# OBD_Reader.net
KiCad netlist of a schematic drawn in EAGLE
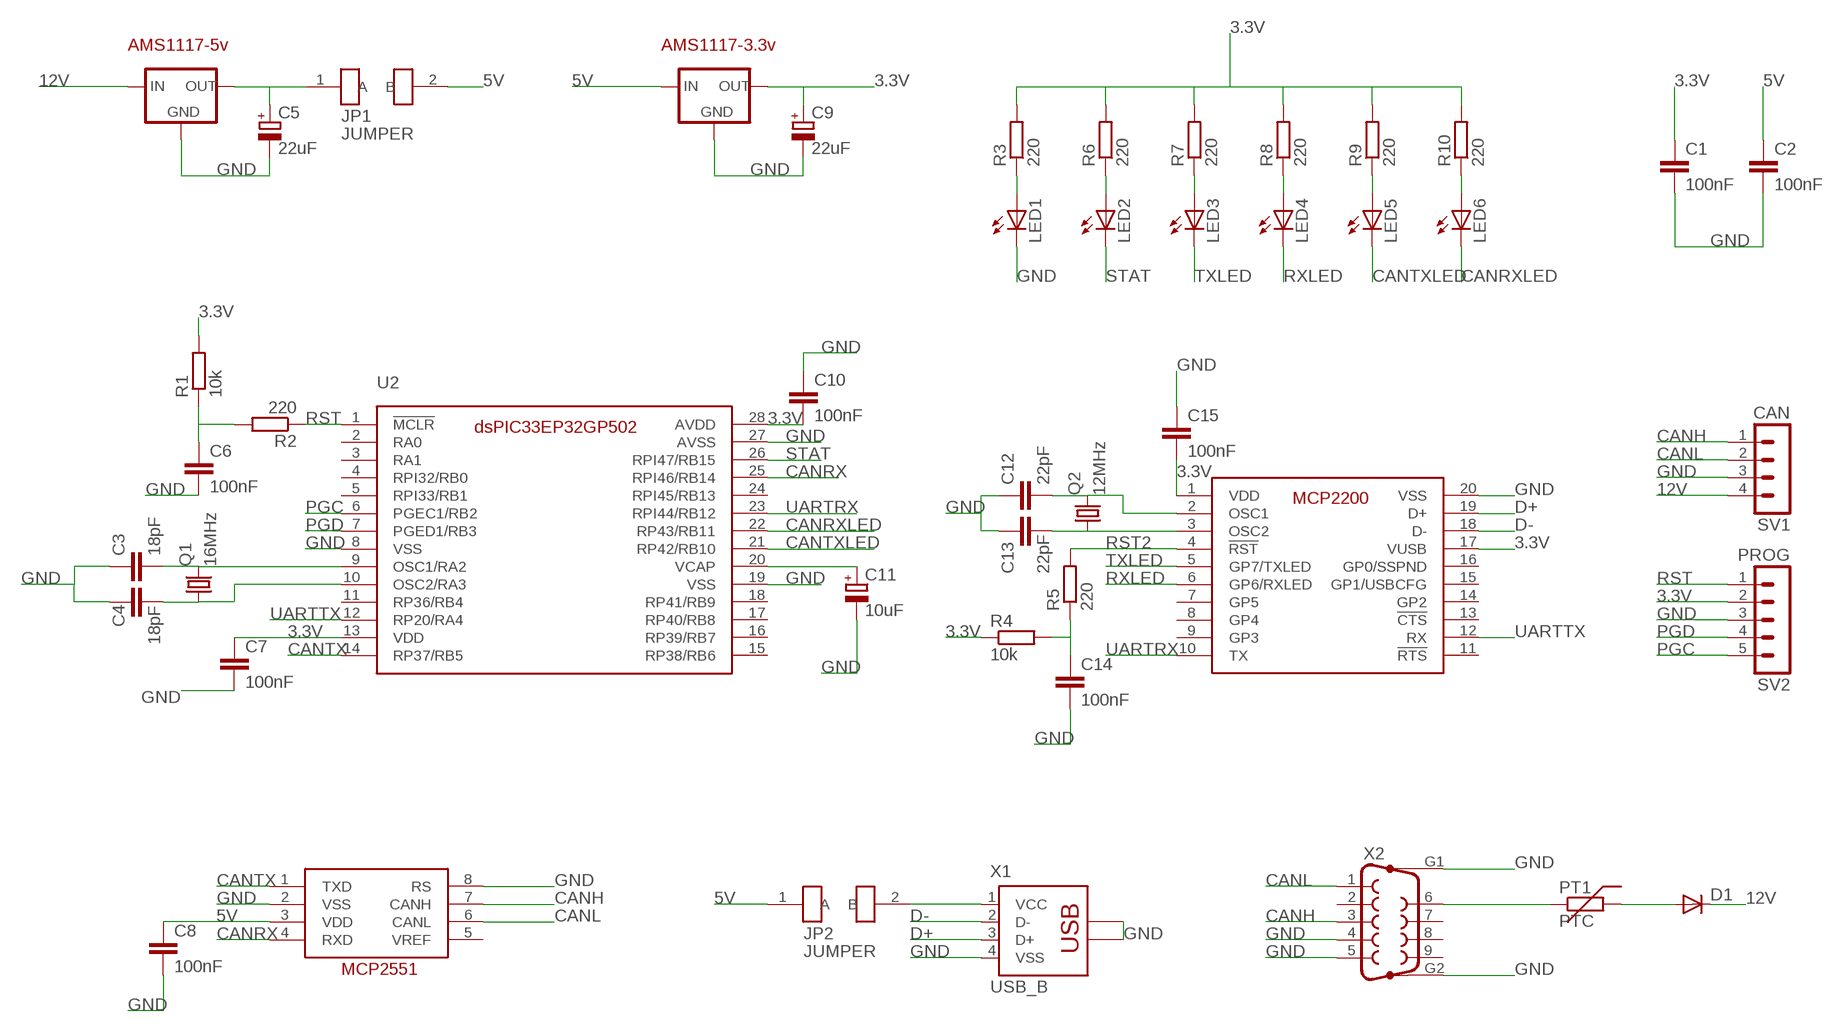
[diagram p0: schematic, sheet 1]

(export (version "E")
  (design (tool "Eeschema 10.0.6"))
  (components
    (comp (ref "C1")
      (value "100nF")
      (footprint "eagle-import:C0603")
      (libsource (lib "eagle-import") (part "C-EUC0603"))
    )
    (comp (ref "C2")
      (value "100nF")
      (footprint "eagle-import:C0603")
      (libsource (lib "eagle-import") (part "C-EUC0603"))
    )
    (comp (ref "C3")
      (value "18pF")
      (footprint "eagle-import:C0603")
      (libsource (lib "eagle-import") (part "C-EUC0603"))
    )
    (comp (ref "C4")
      (value "18pF")
      (footprint "eagle-import:C0603")
      (libsource (lib "eagle-import") (part "C-EUC0603"))
    )
    (comp (ref "C5")
      (value "22uF")
      (footprint "eagle-import:CT3216")
      (libsource (lib "eagle-import") (part "CPOL-EUCT3216"))
    )
    (comp (ref "C6")
      (value "100nF")
      (footprint "eagle-import:C0603")
      (libsource (lib "eagle-import") (part "C-EUC0603"))
    )
    (comp (ref "C7")
      (value "100nF")
      (footprint "eagle-import:C0603")
      (libsource (lib "eagle-import") (part "C-EUC0603"))
    )
    (comp (ref "C8")
      (value "100nF")
      (footprint "eagle-import:C0603")
      (libsource (lib "eagle-import") (part "C-EUC0603"))
    )
    (comp (ref "C9")
      (value "22uF")
      (footprint "eagle-import:CT3216")
      (libsource (lib "eagle-import") (part "CPOL-EUCT3216"))
    )
    (comp (ref "C10")
      (value "100nF")
      (footprint "eagle-import:C0603")
      (libsource (lib "eagle-import") (part "C-EUC0603"))
    )
    (comp (ref "C11")
      (value "10uF")
      (footprint "eagle-import:CT3216")
      (libsource (lib "eagle-import") (part "CPOL-EUCT3216"))
    )
    (comp (ref "C12")
      (value "22pF")
      (footprint "eagle-import:C0603")
      (libsource (lib "eagle-import") (part "C-EUC0603"))
    )
    (comp (ref "C13")
      (value "22pF")
      (footprint "eagle-import:C0603")
      (libsource (lib "eagle-import") (part "C-EUC0603"))
    )
    (comp (ref "C14")
      (value "100nF")
      (footprint "eagle-import:C0603")
      (libsource (lib "eagle-import") (part "C-EUC0603"))
    )
    (comp (ref "C15")
      (value "100nF")
      (footprint "eagle-import:C0603")
      (libsource (lib "eagle-import") (part "C-EUC0603"))
    )
    (comp (ref "D1")
      (value "DIODE-SMB")
      (footprint "eagle-import:SMB")
      (libsource (lib "eagle-import") (part "DIODE-SMB"))
    )
    (comp (ref "JP1")
      (value "JUMPER")
      (footprint "eagle-import:1206")
      (libsource (lib "eagle-import") (part "JUMPER"))
    )
    (comp (ref "JP2")
      (value "JUMPER")
      (footprint "eagle-import:1206")
      (libsource (lib "eagle-import") (part "JUMPER"))
    )
    (comp (ref "LED1")
      (value "LEDCHIPLED_0603")
      (footprint "eagle-import:CHIPLED_0603")
      (libsource (lib "eagle-import") (part "LEDCHIPLED_0603"))
    )
    (comp (ref "LED2")
      (value "LEDCHIPLED_0603")
      (footprint "eagle-import:CHIPLED_0603")
      (libsource (lib "eagle-import") (part "LEDCHIPLED_0603"))
    )
    (comp (ref "LED3")
      (value "LEDCHIPLED_0603")
      (footprint "eagle-import:CHIPLED_0603")
      (libsource (lib "eagle-import") (part "LEDCHIPLED_0603"))
    )
    (comp (ref "LED4")
      (value "LEDCHIPLED_0603")
      (footprint "eagle-import:CHIPLED_0603")
      (libsource (lib "eagle-import") (part "LEDCHIPLED_0603"))
    )
    (comp (ref "LED5")
      (value "LEDCHIPLED_0603")
      (footprint "eagle-import:CHIPLED_0603")
      (libsource (lib "eagle-import") (part "LEDCHIPLED_0603"))
    )
    (comp (ref "LED6")
      (value "LEDCHIPLED_0603")
      (footprint "eagle-import:CHIPLED_0603")
      (libsource (lib "eagle-import") (part "LEDCHIPLED_0603"))
    )
    (comp (ref "PT1")
      (value "PTC")
      (footprint "eagle-import:PTC_1206")
      (libsource (lib "eagle-import") (part "PTC"))
    )
    (comp (ref "Q1")
      (value "16MHz")
      (footprint "eagle-import:HC49_S")
      (libsource (lib "eagle-import") (part "CRYSTALHC49S"))
    )
    (comp (ref "Q2")
      (value "12MHz")
      (footprint "eagle-import:HC49_S")
      (libsource (lib "eagle-import") (part "CRYSTALHC49S"))
    )
    (comp (ref "R1")
      (value "10k")
      (footprint "eagle-import:R0603")
      (libsource (lib "eagle-import") (part "R-EU_R0603"))
    )
    (comp (ref "R2")
      (value "220")
      (footprint "eagle-import:R0603")
      (libsource (lib "eagle-import") (part "R-EU_R0603"))
    )
    (comp (ref "R3")
      (value "220")
      (footprint "eagle-import:R0603")
      (libsource (lib "eagle-import") (part "R-EU_R0603"))
    )
    (comp (ref "R4")
      (value "10k")
      (footprint "eagle-import:R0603")
      (libsource (lib "eagle-import") (part "R-EU_R0603"))
    )
    (comp (ref "R5")
      (value "220")
      (footprint "eagle-import:R0603")
      (libsource (lib "eagle-import") (part "R-EU_R0603"))
    )
    (comp (ref "R6")
      (value "220")
      (footprint "eagle-import:R0603")
      (libsource (lib "eagle-import") (part "R-EU_R0603"))
    )
    (comp (ref "R7")
      (value "220")
      (footprint "eagle-import:R0603")
      (libsource (lib "eagle-import") (part "R-EU_R0603"))
    )
    (comp (ref "R8")
      (value "220")
      (footprint "eagle-import:R0603")
      (libsource (lib "eagle-import") (part "R-EU_R0603"))
    )
    (comp (ref "R9")
      (value "220")
      (footprint "eagle-import:R0603")
      (libsource (lib "eagle-import") (part "R-EU_R0603"))
    )
    (comp (ref "R10")
      (value "220")
      (footprint "eagle-import:R0603")
      (libsource (lib "eagle-import") (part "R-EU_R0603"))
    )
    (comp (ref "SV1")
      (value "CAN")
      (footprint "eagle-import:MA04-1")
      (libsource (lib "eagle-import") (part "MA04-1"))
    )
    (comp (ref "SV2")
      (value "PROG")
      (footprint "eagle-import:MA05-1")
      (libsource (lib "eagle-import") (part "MA05-1"))
    )
    (comp (ref "U1")
      (value "AMS1117_5V")
      (footprint "eagle-import:SOT-223")
      (libsource (lib "eagle-import") (part "AMS1117_5V"))
    )
    (comp (ref "U2")
      (value "DSPIC33EP32GP502")
      (footprint "eagle-import:SSOP28")
      (libsource (lib "eagle-import") (part "DSPIC33EP32GP502"))
    )
    (comp (ref "U3")
      (value "MCP2551")
      (footprint "eagle-import:SOIC20")
      (libsource (lib "eagle-import") (part "MCP2551"))
    )
    (comp (ref "U4")
      (value "AMS1117_3.3V")
      (footprint "eagle-import:SOT-223")
      (libsource (lib "eagle-import") (part "AMS1117_3.3V"))
    )
    (comp (ref "U5")
      (value "MCP2200")
      (footprint "eagle-import:SSOP20")
      (libsource (lib "eagle-import") (part "MCP2200"))
    )
    (comp (ref "X1")
      (value "USB_B")
      (footprint "eagle-import:85-32004-00X")
      (libsource (lib "eagle-import") (part "USB_B"))
    )
    (comp (ref "X2")
      (value "F09HP")
      (footprint "eagle-import:F09HP")
      (libsource (lib "eagle-import") (part "F09HP"))
    )
  )
  (nets
    (net (code "1") (name "/3.3V") (class "Default")
      (node (ref "C1") (pin "1") (pinfunction "1_1") (pintype "passive"))
      (node (ref "C10") (pin "2") (pinfunction "2_2") (pintype "passive"))
      (node (ref "C15") (pin "2") (pinfunction "2_2") (pintype "passive"))
      (node (ref "C7") (pin "1") (pinfunction "1_1") (pintype "passive"))
      (node (ref "C9") (pin "+") (pinfunction "+_+") (pintype "passive"))
      (node (ref "R1") (pin "2") (pinfunction "2_2") (pintype "passive"))
      (node (ref "R10") (pin "2") (pinfunction "2_2") (pintype "passive"))
      (node (ref "R3") (pin "2") (pinfunction "2_2") (pintype "passive"))
      (node (ref "R4") (pin "1") (pinfunction "1_1") (pintype "passive"))
      (node (ref "R6") (pin "2") (pinfunction "2_2") (pintype "passive"))
      (node (ref "R7") (pin "2") (pinfunction "2_2") (pintype "passive"))
      (node (ref "R8") (pin "2") (pinfunction "2_2") (pintype "passive"))
      (node (ref "R9") (pin "2") (pinfunction "2_2") (pintype "passive"))
      (node (ref "SV2") (pin "2") (pinfunction "2_2") (pintype "passive"))
      (node (ref "U2") (pin "13") (pinfunction "VDD_13") (pintype "power_in"))
      (node (ref "U2") (pin "28") (pinfunction "AVDD_28") (pintype "power_in"))
      (node (ref "U4") (pin "2") (pinfunction "OUT_2") (pintype "passive"))
      (node (ref "U5") (pin "1") (pinfunction "VDD_1") (pintype "power_in"))
      (node (ref "U5") (pin "17") (pinfunction "VUSB_17") (pintype "power_in"))
    )
    (net (code "2") (name "/5V") (class "Default")
      (node (ref "C2") (pin "1") (pinfunction "1_1") (pintype "passive"))
      (node (ref "C8") (pin "1") (pinfunction "1_1") (pintype "passive"))
      (node (ref "JP1") (pin "2") (pinfunction "B_2") (pintype "power_in"))
      (node (ref "JP2") (pin "1") (pinfunction "A_1") (pintype "power_in"))
      (node (ref "U3") (pin "3") (pinfunction "VDD_3") (pintype "power_in"))
      (node (ref "U4") (pin "3") (pinfunction "IN_3") (pintype "input"))
    )
    (net (code "3") (name "/12V") (class "Default")
      (node (ref "D1") (pin "C") (pinfunction "C_C") (pintype "passive"))
      (node (ref "SV1") (pin "4") (pinfunction "4_4") (pintype "passive"))
      (node (ref "U1") (pin "3") (pinfunction "IN_3") (pintype "input"))
    )
    (net (code "4") (name "/CANH") (class "Default")
      (node (ref "SV1") (pin "1") (pinfunction "1_1") (pintype "passive"))
      (node (ref "U3") (pin "7") (pinfunction "CANH_7") (pintype "bidirectional"))
      (node (ref "X2") (pin "3") (pinfunction "3_3") (pintype "passive"))
    )
    (net (code "5") (name "/CANL") (class "Default")
      (node (ref "SV1") (pin "2") (pinfunction "2_2") (pintype "passive"))
      (node (ref "U3") (pin "6") (pinfunction "CANL_6") (pintype "bidirectional"))
      (node (ref "X2") (pin "1") (pinfunction "1_1") (pintype "passive"))
    )
    (net (code "6") (name "/CANRX") (class "Default")
      (node (ref "U2") (pin "25") (pinfunction "RPI46/RB14_25") (pintype "bidirectional"))
      (node (ref "U3") (pin "4") (pinfunction "RXD_4") (pintype "bidirectional"))
    )
    (net (code "7") (name "/CANRXLED") (class "Default")
      (node (ref "LED6") (pin "C") (pinfunction "C_C") (pintype "passive"))
      (node (ref "U2") (pin "22") (pinfunction "RP43/RB11_22") (pintype "bidirectional"))
    )
    (net (code "8") (name "/CANTX") (class "Default")
      (node (ref "U2") (pin "14") (pinfunction "RP37/RB5_14") (pintype "bidirectional"))
      (node (ref "U3") (pin "1") (pinfunction "TXD_1") (pintype "bidirectional"))
    )
    (net (code "9") (name "/CANTXLED") (class "Default")
      (node (ref "LED5") (pin "C") (pinfunction "C_C") (pintype "passive"))
      (node (ref "U2") (pin "21") (pinfunction "RP42/RB10_21") (pintype "bidirectional"))
    )
    (net (code "10") (name "/D+") (class "Default")
      (node (ref "U5") (pin "19") (pinfunction "D+_19") (pintype "bidirectional"))
      (node (ref "X1") (pin "3") (pinfunction "D+_3") (pintype "passive"))
    )
    (net (code "11") (name "/D-") (class "Default")
      (node (ref "U5") (pin "18") (pinfunction "D-_18") (pintype "bidirectional"))
      (node (ref "X1") (pin "2") (pinfunction "D-_2") (pintype "passive"))
    )
    (net (code "12") (name "/GND") (class "Default")
      (node (ref "C1") (pin "2") (pinfunction "2_2") (pintype "passive"))
      (node (ref "C10") (pin "1") (pinfunction "1_1") (pintype "passive"))
      (node (ref "C11") (pin "-") (pinfunction "-_-") (pintype "passive"))
      (node (ref "C12") (pin "1") (pinfunction "1_1") (pintype "passive"))
      (node (ref "C13") (pin "1") (pinfunction "1_1") (pintype "passive"))
      (node (ref "C14") (pin "2") (pinfunction "2_2") (pintype "passive"))
      (node (ref "C15") (pin "1") (pinfunction "1_1") (pintype "passive"))
      (node (ref "C2") (pin "2") (pinfunction "2_2") (pintype "passive"))
      (node (ref "C3") (pin "1") (pinfunction "1_1") (pintype "passive"))
      (node (ref "C4") (pin "1") (pinfunction "1_1") (pintype "passive"))
      (node (ref "C5") (pin "-") (pinfunction "-_-") (pintype "passive"))
      (node (ref "C6") (pin "2") (pinfunction "2_2") (pintype "passive"))
      (node (ref "C7") (pin "2") (pinfunction "2_2") (pintype "passive"))
      (node (ref "C8") (pin "2") (pinfunction "2_2") (pintype "passive"))
      (node (ref "C9") (pin "-") (pinfunction "-_-") (pintype "passive"))
      (node (ref "LED1") (pin "C") (pinfunction "C_C") (pintype "passive"))
      (node (ref "SV1") (pin "3") (pinfunction "3_3") (pintype "passive"))
      (node (ref "SV2") (pin "3") (pinfunction "3_3") (pintype "passive"))
      (node (ref "U1") (pin "1") (pinfunction "GND_1") (pintype "input"))
      (node (ref "U2") (pin "19") (pinfunction "VSS_19") (pintype "power_in"))
      (node (ref "U2") (pin "27") (pinfunction "AVSS_27") (pintype "power_in"))
      (node (ref "U2") (pin "8") (pinfunction "VSS_8") (pintype "power_in"))
      (node (ref "U3") (pin "2") (pinfunction "VSS_2") (pintype "power_in"))
      (node (ref "U3") (pin "8") (pinfunction "RS_8") (pintype "bidirectional"))
      (node (ref "U4") (pin "1") (pinfunction "GND_1") (pintype "input"))
      (node (ref "U5") (pin "20") (pinfunction "VSS_20") (pintype "power_in"))
      (node (ref "X1") (pin "4") (pinfunction "VSS_4") (pintype "passive"))
      (node (ref "X1") (pin "M1") (pinfunction "C1_M1") (pintype "bidirectional"))
      (node (ref "X1") (pin "M2") (pinfunction "C2_M2") (pintype "bidirectional"))
      (node (ref "X2") (pin "4") (pinfunction "4_4") (pintype "passive"))
      (node (ref "X2") (pin "5") (pinfunction "5_5") (pintype "passive"))
      (node (ref "X2") (pin "G1") (pinfunction "G1_G1") (pintype "passive"))
      (node (ref "X2") (pin "G2") (pinfunction "G2_G2") (pintype "passive"))
    )
    (net (code "13") (name "/PGC") (class "Default")
      (node (ref "SV2") (pin "5") (pinfunction "5_5") (pintype "passive"))
      (node (ref "U2") (pin "6") (pinfunction "PGEC1/RB2_6") (pintype "bidirectional"))
    )
    (net (code "14") (name "/PGD") (class "Default")
      (node (ref "SV2") (pin "4") (pinfunction "4_4") (pintype "passive"))
      (node (ref "U2") (pin "7") (pinfunction "PGED1/RB3_7") (pintype "bidirectional"))
    )
    (net (code "15") (name "/RST") (class "Default")
      (node (ref "R2") (pin "1") (pinfunction "1_1") (pintype "passive"))
      (node (ref "SV2") (pin "1") (pinfunction "1_1") (pintype "passive"))
      (node (ref "U2") (pin "1") (pinfunction "~{MCLR}_1") (pintype "input"))
    )
    (net (code "16") (name "/RST2") (class "Default")
      (node (ref "R5") (pin "2") (pinfunction "2_2") (pintype "passive"))
      (node (ref "U5") (pin "4") (pinfunction "~{RST}_4") (pintype "input"))
    )
    (net (code "17") (name "/RXLED") (class "Default")
      (node (ref "LED4") (pin "C") (pinfunction "C_C") (pintype "passive"))
      (node (ref "U5") (pin "6") (pinfunction "GP6/RXLED_6") (pintype "bidirectional"))
    )
    (net (code "18") (name "/STAT") (class "Default")
      (node (ref "LED2") (pin "C") (pinfunction "C_C") (pintype "passive"))
      (node (ref "U2") (pin "26") (pinfunction "RPI47/RB15_26") (pintype "bidirectional"))
    )
    (net (code "19") (name "/TXLED") (class "Default")
      (node (ref "LED3") (pin "C") (pinfunction "C_C") (pintype "passive"))
      (node (ref "U5") (pin "5") (pinfunction "GP7/TXLED_5") (pintype "bidirectional"))
    )
    (net (code "20") (name "/UARTRX") (class "Default")
      (node (ref "U2") (pin "23") (pinfunction "RPI44/RB12_23") (pintype "bidirectional"))
      (node (ref "U5") (pin "10") (pinfunction "TX_10") (pintype "bidirectional"))
    )
    (net (code "21") (name "/UARTTX") (class "Default")
      (node (ref "U2") (pin "12") (pinfunction "RP20/RA4_12") (pintype "bidirectional"))
      (node (ref "U5") (pin "12") (pinfunction "RX_12") (pintype "bidirectional"))
    )
    (net (code "22") (name "Net-(C6-Pad1)") (class "Default")
      (node (ref "C6") (pin "1") (pinfunction "1_1") (pintype "passive"))
      (node (ref "R1") (pin "1") (pinfunction "1_1") (pintype "passive"))
      (node (ref "R2") (pin "2") (pinfunction "2_2") (pintype "passive"))
    )
    (net (code "23") (name "Net-(C14-Pad1)") (class "Default")
      (node (ref "C14") (pin "1") (pinfunction "1_1") (pintype "passive"))
      (node (ref "R4") (pin "2") (pinfunction "2_2") (pintype "passive"))
      (node (ref "R5") (pin "1") (pinfunction "1_1") (pintype "passive"))
    )
    (net (code "24") (name "Net-(D1-PadA)") (class "Default")
      (node (ref "D1") (pin "A") (pinfunction "A_A") (pintype "passive"))
      (node (ref "PT1") (pin "2") (pinfunction "2_2") (pintype "passive"))
    )
    (net (code "25") (name "Net-(JP1-A)") (class "Default")
      (node (ref "C5") (pin "+") (pinfunction "+_+") (pintype "passive"))
      (node (ref "JP1") (pin "1") (pinfunction "A_1") (pintype "power_in"))
      (node (ref "U1") (pin "2") (pinfunction "OUT_2") (pintype "passive"))
    )
    (net (code "26") (name "Net-(JP2-B)") (class "Default")
      (node (ref "JP2") (pin "2") (pinfunction "B_2") (pintype "power_in"))
      (node (ref "X1") (pin "1") (pinfunction "VCC_1") (pintype "passive"))
    )
    (net (code "27") (name "Net-(LED1-PadA)") (class "Default")
      (node (ref "LED1") (pin "A") (pinfunction "A_A") (pintype "passive"))
      (node (ref "R3") (pin "1") (pinfunction "1_1") (pintype "passive"))
    )
    (net (code "28") (name "Net-(LED2-PadA)") (class "Default")
      (node (ref "LED2") (pin "A") (pinfunction "A_A") (pintype "passive"))
      (node (ref "R6") (pin "1") (pinfunction "1_1") (pintype "passive"))
    )
    (net (code "29") (name "Net-(LED3-PadA)") (class "Default")
      (node (ref "LED3") (pin "A") (pinfunction "A_A") (pintype "passive"))
      (node (ref "R7") (pin "1") (pinfunction "1_1") (pintype "passive"))
    )
    (net (code "30") (name "Net-(LED4-PadA)") (class "Default")
      (node (ref "LED4") (pin "A") (pinfunction "A_A") (pintype "passive"))
      (node (ref "R8") (pin "1") (pinfunction "1_1") (pintype "passive"))
    )
    (net (code "31") (name "Net-(LED5-PadA)") (class "Default")
      (node (ref "LED5") (pin "A") (pinfunction "A_A") (pintype "passive"))
      (node (ref "R9") (pin "1") (pinfunction "1_1") (pintype "passive"))
    )
    (net (code "32") (name "Net-(LED6-PadA)") (class "Default")
      (node (ref "LED6") (pin "A") (pinfunction "A_A") (pintype "passive"))
      (node (ref "R10") (pin "1") (pinfunction "1_1") (pintype "passive"))
    )
    (net (code "33") (name "Net-(PT1-Pad1)") (class "Default")
      (node (ref "PT1") (pin "1") (pinfunction "1_1") (pintype "passive"))
      (node (ref "X2") (pin "6") (pinfunction "6_6") (pintype "passive"))
    )
    (net (code "34") (name "Net-(U2-OSC1{slash}RA2)") (class "Default")
      (node (ref "C3") (pin "2") (pinfunction "2_2") (pintype "passive"))
      (node (ref "Q1") (pin "2") (pinfunction "2_2") (pintype "passive"))
      (node (ref "U2") (pin "9") (pinfunction "OSC1/RA2_9") (pintype "bidirectional"))
    )
    (net (code "35") (name "Net-(U2-OSC2{slash}RA3)") (class "Default")
      (node (ref "C4") (pin "2") (pinfunction "2_2") (pintype "passive"))
      (node (ref "Q1") (pin "1") (pinfunction "1_1") (pintype "passive"))
      (node (ref "U2") (pin "10") (pinfunction "OSC2/RA3_10") (pintype "bidirectional"))
    )
    (net (code "36") (name "Net-(U2-VCAP)") (class "Default")
      (node (ref "C11") (pin "+") (pinfunction "+_+") (pintype "passive"))
      (node (ref "U2") (pin "20") (pinfunction "VCAP_20") (pintype "power_in"))
    )
    (net (code "37") (name "Net-(U5-OSC1)") (class "Default")
      (node (ref "C12") (pin "2") (pinfunction "2_2") (pintype "passive"))
      (node (ref "Q2") (pin "2") (pinfunction "2_2") (pintype "passive"))
      (node (ref "U5") (pin "2") (pinfunction "OSC1_2") (pintype "bidirectional"))
    )
    (net (code "38") (name "Net-(U5-OSC2)") (class "Default")
      (node (ref "C13") (pin "2") (pinfunction "2_2") (pintype "passive"))
      (node (ref "Q2") (pin "1") (pinfunction "1_1") (pintype "passive"))
      (node (ref "U5") (pin "3") (pinfunction "OSC2_3") (pintype "bidirectional"))
    )
    (net (code "39") (name "unconnected-(U2-RA0-Pad2)") (class "Default")
      (node (ref "U2") (pin "2") (pinfunction "RA0_2") (pintype "bidirectional"))
    )
    (net (code "40") (name "unconnected-(U2-RA1-Pad3)") (class "Default")
      (node (ref "U2") (pin "3") (pinfunction "RA1_3") (pintype "bidirectional"))
    )
    (net (code "41") (name "unconnected-(U2-RP36{slash}RB4-Pad11)") (class "Default")
      (node (ref "U2") (pin "11") (pinfunction "RP36/RB4_11") (pintype "bidirectional"))
    )
    (net (code "42") (name "unconnected-(U2-RP38{slash}RB6-Pad15)") (class "Default")
      (node (ref "U2") (pin "15") (pinfunction "RP38/RB6_15") (pintype "bidirectional"))
    )
    (net (code "43") (name "unconnected-(U2-RP39{slash}RB7-Pad16)") (class "Default")
      (node (ref "U2") (pin "16") (pinfunction "RP39/RB7_16") (pintype "bidirectional"))
    )
    (net (code "44") (name "unconnected-(U2-RP40{slash}RB8-Pad17)") (class "Default")
      (node (ref "U2") (pin "17") (pinfunction "RP40/RB8_17") (pintype "bidirectional"))
    )
    (net (code "45") (name "unconnected-(U2-RP41{slash}RB9-Pad18)") (class "Default")
      (node (ref "U2") (pin "18") (pinfunction "RP41/RB9_18") (pintype "bidirectional"))
    )
    (net (code "46") (name "unconnected-(U2-RPI32{slash}RB0-Pad4)") (class "Default")
      (node (ref "U2") (pin "4") (pinfunction "RPI32/RB0_4") (pintype "bidirectional"))
    )
    (net (code "47") (name "unconnected-(U2-RPI33{slash}RB1-Pad5)") (class "Default")
      (node (ref "U2") (pin "5") (pinfunction "RPI33/RB1_5") (pintype "bidirectional"))
    )
    (net (code "48") (name "unconnected-(U2-RPI45{slash}RB13-Pad24)") (class "Default")
      (node (ref "U2") (pin "24") (pinfunction "RPI45/RB13_24") (pintype "bidirectional"))
    )
    (net (code "49") (name "unconnected-(U3-VREF-Pad5)") (class "Default")
      (node (ref "U3") (pin "5") (pinfunction "VREF_5") (pintype "input"))
    )
    (net (code "50") (name "unconnected-(U5-GP0{slash}SSPND-Pad16)") (class "Default")
      (node (ref "U5") (pin "16") (pinfunction "GP0/SSPND_16") (pintype "bidirectional"))
    )
    (net (code "51") (name "unconnected-(U5-GP1{slash}USBCFG-Pad15)") (class "Default")
      (node (ref "U5") (pin "15") (pinfunction "GP1/USBCFG_15") (pintype "bidirectional"))
    )
    (net (code "52") (name "unconnected-(U5-GP2-Pad14)") (class "Default")
      (node (ref "U5") (pin "14") (pinfunction "GP2_14") (pintype "bidirectional"))
    )
    (net (code "53") (name "unconnected-(U5-GP3-Pad9)") (class "Default")
      (node (ref "U5") (pin "9") (pinfunction "GP3_9") (pintype "bidirectional"))
    )
    (net (code "54") (name "unconnected-(U5-GP4-Pad8)") (class "Default")
      (node (ref "U5") (pin "8") (pinfunction "GP4_8") (pintype "bidirectional"))
    )
    (net (code "55") (name "unconnected-(U5-GP5-Pad7)") (class "Default")
      (node (ref "U5") (pin "7") (pinfunction "GP5_7") (pintype "bidirectional"))
    )
    (net (code "56") (name "unconnected-(U5-~{CTS}-Pad13)") (class "Default")
      (node (ref "U5") (pin "13") (pinfunction "~{CTS}_13") (pintype "bidirectional"))
    )
    (net (code "57") (name "unconnected-(U5-~{RTS}-Pad11)") (class "Default")
      (node (ref "U5") (pin "11") (pinfunction "~{RTS}_11") (pintype "bidirectional"))
    )
    (net (code "58") (name "unconnected-(X2-Pad2)") (class "Default")
      (node (ref "X2") (pin "2") (pinfunction "2_2") (pintype "passive"))
    )
    (net (code "59") (name "unconnected-(X2-Pad7)") (class "Default")
      (node (ref "X2") (pin "7") (pinfunction "7_7") (pintype "passive"))
    )
    (net (code "60") (name "unconnected-(X2-Pad8)") (class "Default")
      (node (ref "X2") (pin "8") (pinfunction "8_8") (pintype "passive"))
    )
    (net (code "61") (name "unconnected-(X2-Pad9)") (class "Default")
      (node (ref "X2") (pin "9") (pinfunction "9_9") (pintype "passive"))
    )
  )
)
